# pc_mlx90632_brk.net
KiCad netlist of a schematic drawn in EAGLE
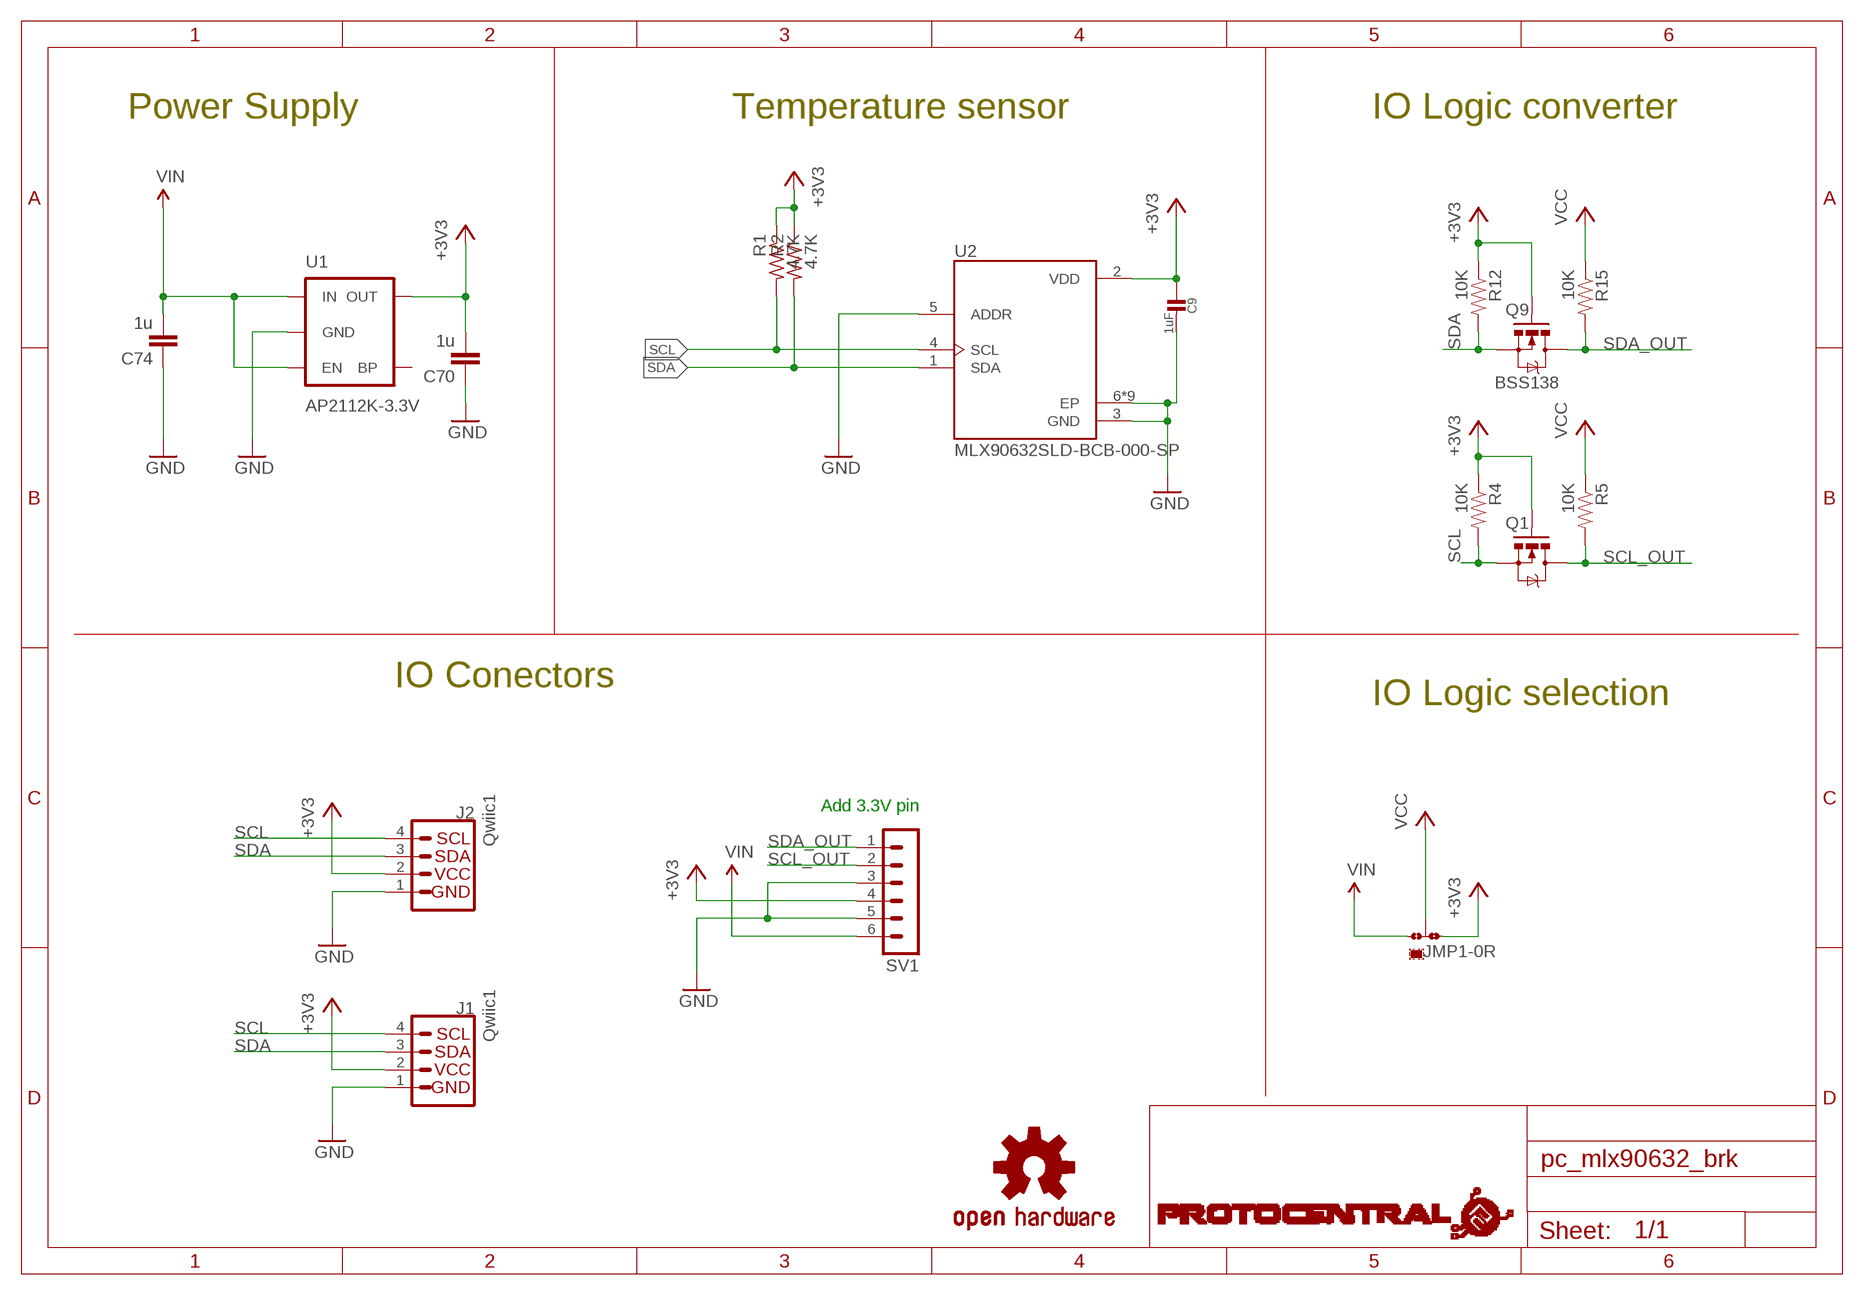
[diagram p0: schematic, sheet 1]

(export (version "E")
  (design (tool "Eeschema 10.0.6"))
  (components
    (comp (ref "C9")
      (value "1uF")
      (footprint "eagle-import:_0402")
      (libsource (lib "eagle-import") (part "CAP_CERAMIC_0402"))
    )
    (comp (ref "C70")
      (value "1u")
      (footprint "eagle-import:C0805")
      (libsource (lib "eagle-import") (part "C-EUC0805"))
    )
    (comp (ref "C74")
      (value "1u")
      (footprint "eagle-import:C0805")
      (libsource (lib "eagle-import") (part "C-EUC0805"))
    )
    (comp (ref "J1")
      (value "Qwiic1")
      (footprint "eagle-import:1X04_1MM_RA")
      (libsource (lib "eagle-import") (part "QWIIC_CONNECTORJS-1MM"))
    )
    (comp (ref "J2")
      (value "Qwiic1")
      (footprint "eagle-import:1X04_1MM_RA")
      (libsource (lib "eagle-import") (part "QWIIC_CONNECTORJS-1MM"))
    )
    (comp (ref "JMP1")
      (value "0R-JUMPA")
      (footprint "eagle-import:A0R-JMP-0402")
      (libsource (lib "eagle-import") (part "0R-JUMPA"))
    )
    (comp (ref "Q1")
      (value "BSS138")
      (footprint "eagle-import:SOT23-3")
      (libsource (lib "eagle-import") (part "MOSFET-NCHANNELSMD"))
    )
    (comp (ref "Q9")
      (value "BSS138")
      (footprint "eagle-import:SOT23-3")
      (libsource (lib "eagle-import") (part "MOSFET-NCHANNELSMD"))
    )
    (comp (ref "R1")
      (value "4.7K")
      (footprint "eagle-import:R0402")
      (libsource (lib "eagle-import") (part "R-US_R0402"))
    )
    (comp (ref "R2")
      (value "4.7K")
      (footprint "eagle-import:R0402")
      (libsource (lib "eagle-import") (part "R-US_R0402"))
    )
    (comp (ref "R4")
      (value "10K")
      (footprint "eagle-import:0805")
      (libsource (lib "eagle-import") (part "RESISTOR0805-RES"))
    )
    (comp (ref "R5")
      (value "10K")
      (footprint "eagle-import:0805")
      (libsource (lib "eagle-import") (part "RESISTOR0805-RES"))
    )
    (comp (ref "R12")
      (value "10K")
      (footprint "eagle-import:0805")
      (libsource (lib "eagle-import") (part "RESISTOR0805-RES"))
    )
    (comp (ref "R15")
      (value "10K")
      (footprint "eagle-import:0805")
      (libsource (lib "eagle-import") (part "RESISTOR0805-RES"))
    )
    (comp (ref "SV1")
      (value "MA06-1")
      (footprint "eagle-import:MA06-1")
      (libsource (lib "eagle-import") (part "MA06-1"))
    )
    (comp (ref "U$5")
      (value "PROTY-LOGO")
      (footprint "eagle-import:LOGO-PROTY")
      (libsource (lib "eagle-import") (part "PROTY-LOGO"))
    )
    (comp (ref "U$7")
      (value "OSHW-LOGOS")
      (footprint "eagle-import:OSHW-LOGO-S")
      (libsource (lib "eagle-import") (part "OSHW-LOGOS"))
    )
    (comp (ref "U1")
      (value "AP2112K-3.3V")
      (footprint "eagle-import:SOT23-5")
      (libsource (lib "eagle-import") (part "V_REG_LDOSMD"))
    )
    (comp (ref "U2")
      (value "MLX90632SLD-BCB-000-SP")
      (footprint "eagle-import:XDCR_MLX90632SLD-BCB-000-SP")
      (fields
        (field (name "DIGI-KEY_PART_NUMBER") "MLX90632SLD-BCB-000-SP-ND")
        (field (name "MF") "Melexis Technologies")
      )
      (libsource (lib "eagle-import") (part "MLX90632SLD-BCB-000-SP"))
    )
  )
  (nets
    (net (code "1") (name "+3V3") (class "Default")
      (node (ref "C70") (pin "2") (pinfunction "2_2") (pintype "passive"))
      (node (ref "C9") (pin "1") (pinfunction "1_1") (pintype "passive"))
      (node (ref "J1") (pin "2") (pinfunction "2_2") (pintype "power_in"))
      (node (ref "J2") (pin "2") (pinfunction "2_2") (pintype "power_in"))
      (node (ref "JMP1") (pin "3") (pinfunction "3_3") (pintype "passive"))
      (node (ref "Q1") (pin "1") (pinfunction "G_1") (pintype "passive"))
      (node (ref "Q9") (pin "1") (pinfunction "G_1") (pintype "passive"))
      (node (ref "R1") (pin "1") (pinfunction "1_1") (pintype "passive"))
      (node (ref "R12") (pin "1") (pinfunction "1_1") (pintype "passive"))
      (node (ref "R2") (pin "1") (pinfunction "1_1") (pintype "passive"))
      (node (ref "R4") (pin "1") (pinfunction "1_1") (pintype "passive"))
      (node (ref "SV1") (pin "4") (pinfunction "4_4") (pintype "passive"))
      (node (ref "U1") (pin "5") (pinfunction "OUT_5") (pintype "passive"))
      (node (ref "U2") (pin "2") (pinfunction "VDD_2") (pintype "power_in"))
    )
    (net (code "2") (name "/SCL_OUT") (class "Default")
      (node (ref "Q1") (pin "3") (pinfunction "D_3") (pintype "passive"))
      (node (ref "R5") (pin "2") (pinfunction "2_2") (pintype "passive"))
      (node (ref "SV1") (pin "2") (pinfunction "2_2") (pintype "passive"))
    )
    (net (code "3") (name "/SDA_OUT") (class "Default")
      (node (ref "Q9") (pin "3") (pinfunction "D_3") (pintype "passive"))
      (node (ref "R15") (pin "2") (pinfunction "2_2") (pintype "passive"))
      (node (ref "SV1") (pin "1") (pinfunction "1_1") (pintype "passive"))
    )
    (net (code "4") (name "GND") (class "Default")
      (node (ref "C70") (pin "1") (pinfunction "1_1") (pintype "passive"))
      (node (ref "C74") (pin "1") (pinfunction "1_1") (pintype "passive"))
      (node (ref "C9") (pin "2") (pinfunction "2_2") (pintype "passive"))
      (node (ref "J1") (pin "1") (pinfunction "1_1") (pintype "power_in"))
      (node (ref "J2") (pin "1") (pinfunction "1_1") (pintype "power_in"))
      (node (ref "SV1") (pin "3") (pinfunction "3_3") (pintype "passive"))
      (node (ref "SV1") (pin "5") (pinfunction "5_5") (pintype "passive"))
      (node (ref "U1") (pin "2") (pinfunction "GND_2") (pintype "input"))
      (node (ref "U2") (pin "3") (pinfunction "GND_3") (pintype "power_in"))
      (node (ref "U2") (pin "5") (pinfunction "ADDR_5") (pintype "input"))
      (node (ref "U2") (pin "6") (pinfunction "EP_6") (pintype "power_in"))
      (node (ref "U2") (pin "6.1") (pinfunction "EP_6.1") (pintype "power_in"))
      (node (ref "U2") (pin "6.2") (pinfunction "EP_6.2") (pintype "power_in"))
      (node (ref "U2") (pin "6.3") (pinfunction "EP_6.3") (pintype "power_in"))
      (node (ref "U2") (pin "6.4") (pinfunction "EP_6.4") (pintype "power_in"))
      (node (ref "U2") (pin "6.5") (pinfunction "EP_6.5") (pintype "power_in"))
      (node (ref "U2") (pin "6.6") (pinfunction "EP_6.6") (pintype "power_in"))
      (node (ref "U2") (pin "6.7") (pinfunction "EP_6.7") (pintype "power_in"))
      (node (ref "U2") (pin "6.8") (pinfunction "EP_6.8") (pintype "power_in"))
    )
    (net (code "5") (name "SCL") (class "Default")
      (node (ref "J1") (pin "4") (pinfunction "4_4") (pintype "passive"))
      (node (ref "J2") (pin "4") (pinfunction "4_4") (pintype "passive"))
      (node (ref "Q1") (pin "2") (pinfunction "S_2") (pintype "passive"))
      (node (ref "R1") (pin "2") (pinfunction "2_2") (pintype "passive"))
      (node (ref "R4") (pin "2") (pinfunction "2_2") (pintype "passive"))
      (node (ref "U2") (pin "4") (pinfunction "SCL_4") (pintype "input"))
    )
    (net (code "6") (name "SDA") (class "Default")
      (node (ref "J1") (pin "3") (pinfunction "3_3") (pintype "passive"))
      (node (ref "J2") (pin "3") (pinfunction "3_3") (pintype "passive"))
      (node (ref "Q9") (pin "2") (pinfunction "S_2") (pintype "passive"))
      (node (ref "R12") (pin "2") (pinfunction "2_2") (pintype "passive"))
      (node (ref "R2") (pin "2") (pinfunction "2_2") (pintype "passive"))
      (node (ref "U2") (pin "1") (pinfunction "SDA_1") (pintype "bidirectional"))
    )
    (net (code "7") (name "VCC") (class "Default")
      (node (ref "JMP1") (pin "2") (pinfunction "2_2") (pintype "passive"))
      (node (ref "R15") (pin "1") (pinfunction "1_1") (pintype "passive"))
      (node (ref "R5") (pin "1") (pinfunction "1_1") (pintype "passive"))
    )
    (net (code "8") (name "VIN") (class "Default")
      (node (ref "C74") (pin "2") (pinfunction "2_2") (pintype "passive"))
      (node (ref "JMP1") (pin "1") (pinfunction "1_1") (pintype "passive"))
      (node (ref "SV1") (pin "6") (pinfunction "6_6") (pintype "passive"))
      (node (ref "U1") (pin "1") (pinfunction "IN_1") (pintype "input"))
      (node (ref "U1") (pin "3") (pinfunction "EN_3") (pintype "input"))
    )
    (net (code "9") (name "unconnected-(U1-BP-Pad4)") (class "Default")
      (node (ref "U1") (pin "4") (pinfunction "BP_4") (pintype "input"))
    )
  )
)
